# Isolator_I2C.net
KiCad netlist of a schematic drawn in Altium Designer
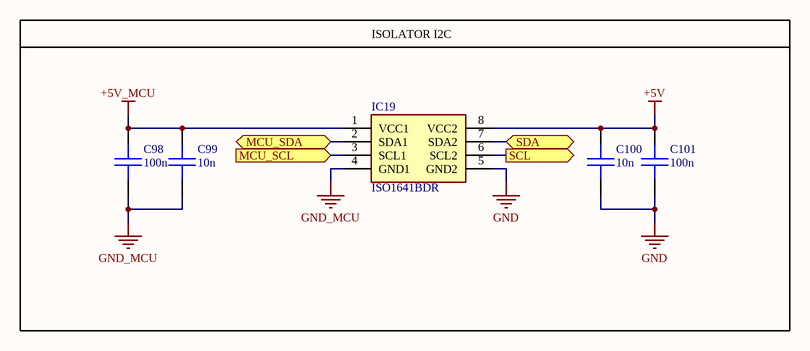
[diagram p0: Isolator_I2C.SchDoc]

(export (version "E")
  (design (tool "Eeschema 10.0.6"))
  (components
    (comp (ref "C98")
      (value "100n")
      (footprint "C_0603")
      (description "SMD Chip Capacitor")
      (libsource (lib "My_Integrated_Lib") (part "CAP"))
    )
    (comp (ref "C99")
      (value "10n")
      (footprint "C_0603")
      (description "SMD Chip Capacitor")
      (libsource (lib "My_Integrated_Lib") (part "CAP"))
    )
    (comp (ref "C100")
      (value "10n")
      (footprint "C_0603")
      (description "SMD Chip Capacitor")
      (libsource (lib "My_Integrated_Lib") (part "CAP"))
    )
    (comp (ref "C101")
      (value "100n")
      (footprint "C_0603")
      (description "SMD Chip Capacitor")
      (libsource (lib "My_Integrated_Lib") (part "CAP"))
    )
    (comp (ref "IC19")
      (value "ISO1641BDR")
      (footprint "SOIC127P600X175-8N")
      (description "Integrated Circuit")
      (fields (field (name "MOUSER PART NUMBER") "595-ISO1641BDR"))
      (libsource (lib "My_Integrated_Lib") (part "ISO1641BDR"))
    )
  )
  (nets
    (net (code "1") (name "+5V") (class "Default")
      (node (ref "C100") (pin "2") (pinfunction "2_2") (pintype "passive"))
      (node (ref "C101") (pin "2") (pinfunction "2_2") (pintype "passive"))
      (node (ref "IC19") (pin "8") (pinfunction "VCC2_8") (pintype "passive"))
    )
    (net (code "2") (name "+5V_MCU") (class "Default")
      (node (ref "C98") (pin "2") (pinfunction "2_2") (pintype "passive"))
      (node (ref "C99") (pin "2") (pinfunction "2_2") (pintype "passive"))
      (node (ref "IC19") (pin "1") (pinfunction "VCC1_1") (pintype "passive"))
    )
    (net (code "3") (name "/MCU_SCL") (class "Default")
      (node (ref "IC19") (pin "3") (pinfunction "SCL1_3") (pintype "passive"))
    )
    (net (code "4") (name "/MCU_SDA") (class "Default")
      (node (ref "IC19") (pin "2") (pinfunction "SDA1_2") (pintype "passive"))
    )
    (net (code "5") (name "/SCL") (class "Default")
      (node (ref "IC19") (pin "6") (pinfunction "SCL2_6") (pintype "passive"))
    )
    (net (code "6") (name "/SDA") (class "Default")
      (node (ref "IC19") (pin "7") (pinfunction "SDA2_7") (pintype "passive"))
    )
    (net (code "7") (name "GND") (class "Default")
      (node (ref "C100") (pin "1") (pinfunction "1_1") (pintype "passive"))
      (node (ref "C101") (pin "1") (pinfunction "1_1") (pintype "passive"))
      (node (ref "IC19") (pin "5") (pinfunction "GND2_5") (pintype "passive"))
    )
    (net (code "8") (name "GND_MCU") (class "Default")
      (node (ref "C98") (pin "1") (pinfunction "1_1") (pintype "passive"))
      (node (ref "C99") (pin "1") (pinfunction "1_1") (pintype "passive"))
      (node (ref "IC19") (pin "4") (pinfunction "GND1_4") (pintype "passive"))
    )
  )
)
